# bob_encoder.net
KiCad netlist of a schematic drawn in Altium Designer
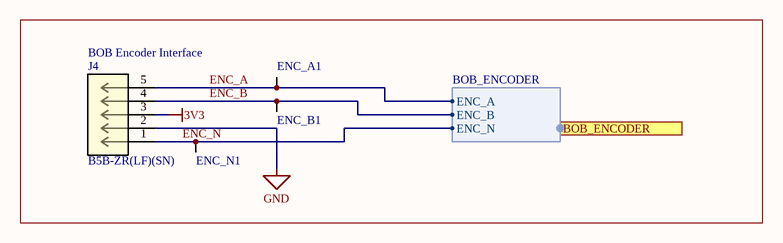
[diagram p0: bob_encoder.SchDoc]

(export (version "E")
  (design (tool "Eeschema 10.0.6"))
  (components
    (comp (ref "ENC_A1")
      (value "Test Point (Via)")
      (footprint "TP")
      (libsource (lib "AltiumLibraries") (part "Test Point (Via)"))
    )
    (comp (ref "ENC_B1")
      (value "Test Point (Via)")
      (footprint "TP")
      (libsource (lib "AltiumLibraries") (part "Test Point (Via)"))
    )
    (comp (ref "ENC_N1")
      (value "Test Point (Via)")
      (footprint "TP")
      (libsource (lib "AltiumLibraries") (part "Test Point (Via)"))
    )
    (comp (ref "J4")
      (value "B5B-ZR(LF)(SN)")
      (footprint "JST_B5B-ZR(LF)(SN)")
      (description "Connector Header Through Hole 5 position 0.059 (1.50mm)")
      (fields (field (name "MF") "JST Sales"))
      (libsource (lib "AltiumLibraries") (part "CN 5POS JST ZR"))
    )
  )
  (nets
    (net (code "2") (name "/ENC_A") (class "Default")
      (node (ref "ENC_A1") (pin "1") (pinfunction "1_1") (pintype "passive"))
      (node (ref "J4") (pin "5") (pinfunction "5_5") (pintype "passive"))
    )
    (net (code "3") (name "/ENC_B") (class "Default")
      (node (ref "ENC_B1") (pin "1") (pinfunction "1_1") (pintype "passive"))
      (node (ref "J4") (pin "4") (pinfunction "4_4") (pintype "passive"))
    )
    (net (code "4") (name "/ENC_N") (class "Default")
      (node (ref "ENC_N1") (pin "1") (pinfunction "1_1") (pintype "passive"))
      (node (ref "J4") (pin "1") (pinfunction "1_1") (pintype "passive"))
    )
    (net (code "6") (name "3V3") (class "Default")
      (node (ref "J4") (pin "3") (pinfunction "3_3") (pintype "passive"))
    )
    (net (code "7") (name "GND") (class "Default")
      (node (ref "J4") (pin "2") (pinfunction "2_2") (pintype "passive"))
    )
  )
)
